# generic_micro_2.net
KiCad netlist of a schematic drawn in EAGLE
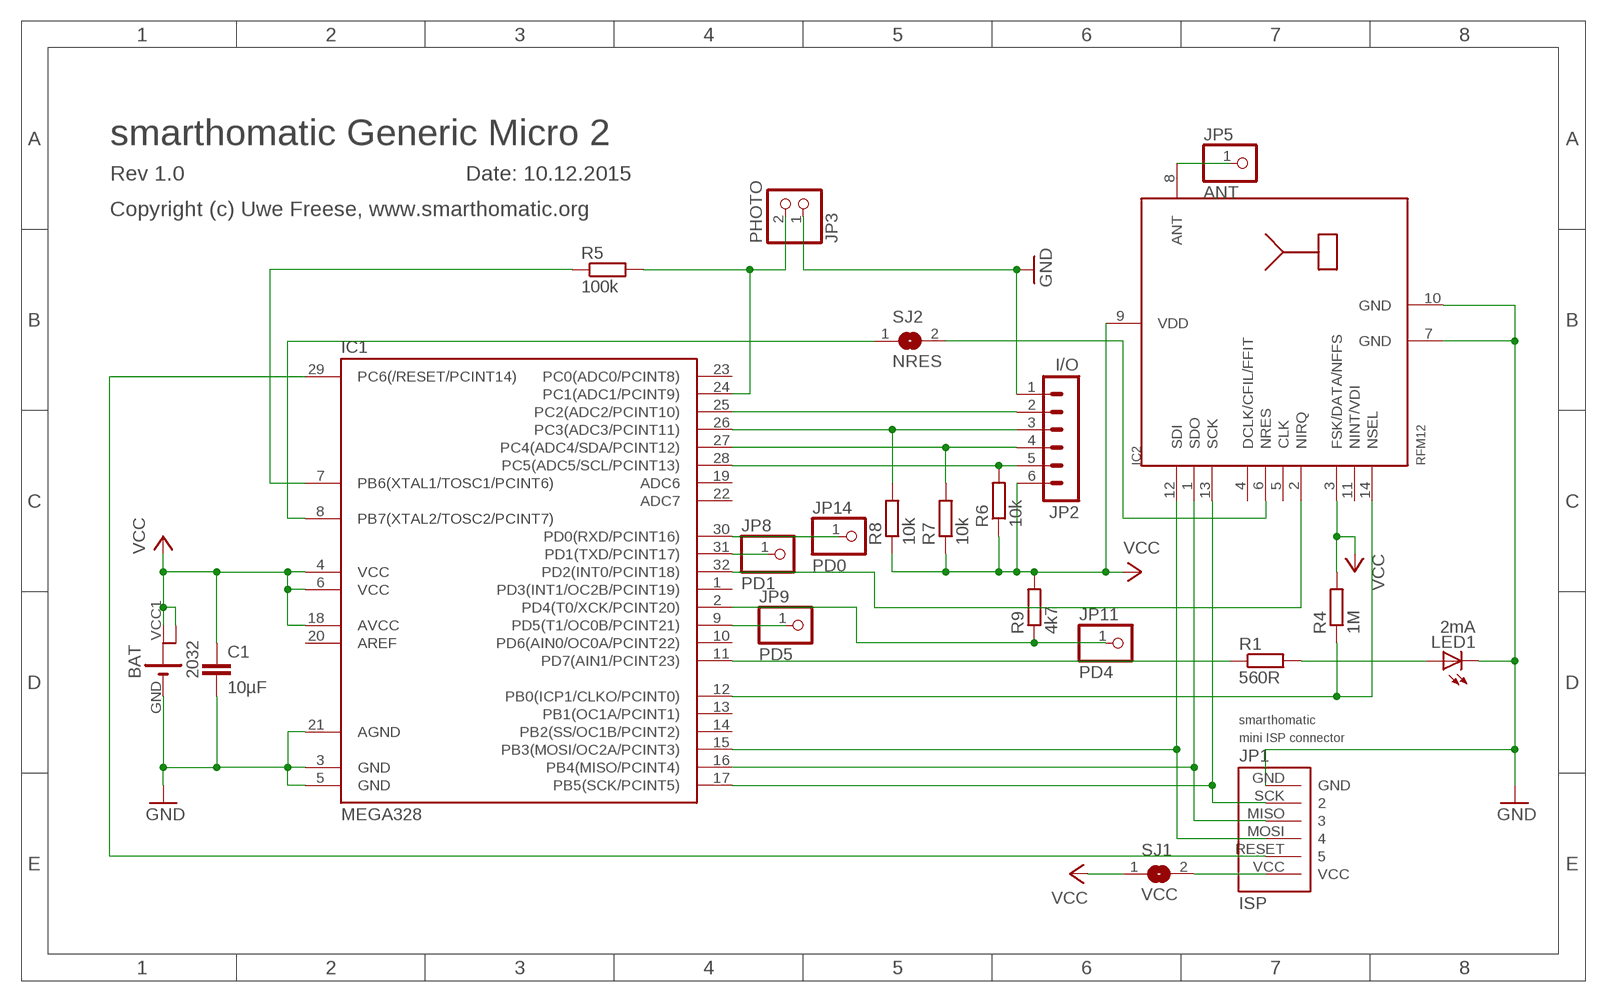
[diagram p0: schematic, sheet 1]

(export (version "E")
  (design (tool "Eeschema 10.0.6"))
  (components
    (comp (ref "BAT")
      (value "2032")
      (footprint "eagle-import:KZH20SMD")
      (libsource (lib "eagle-import") (part "2032"))
    )
    (comp (ref "C1")
      (value "10µF")
      (footprint "eagle-import:C0603")
      (libsource (lib "eagle-import") (part "C-EUC0603"))
    )
    (comp (ref "IC1")
      (value "MEGA328")
      (footprint "eagle-import:TQFP32-08")
      (libsource (lib "eagle-import") (part "MEGA48/88/168-AU"))
    )
    (comp (ref "IC2")
      (value "RFM12")
      (footprint "eagle-import:RFM")
      (libsource (lib "eagle-import") (part "RFM12"))
    )
    (comp (ref "JP1")
      (value "ISP")
      (footprint "eagle-import:PINHD_1X6_1.27")
      (libsource (lib "eagle-import") (part "SHC_MINI_ISPP"))
    )
    (comp (ref "JP2")
      (value "I/O")
      (footprint "eagle-import:MA06-1")
      (libsource (lib "eagle-import") (part "MA06-1"))
    )
    (comp (ref "JP3")
      (value "PHOTO")
      (footprint "eagle-import:1X02")
      (libsource (lib "eagle-import") (part "PINHD-1X2"))
    )
    (comp (ref "JP5")
      (value "ANT")
      (footprint "eagle-import:1X01")
      (libsource (lib "eagle-import") (part "PINHD-1X1"))
    )
    (comp (ref "JP8")
      (value "PD1")
      (footprint "eagle-import:1X01")
      (libsource (lib "eagle-import") (part "PINHD-1X1"))
    )
    (comp (ref "JP9")
      (value "PD5")
      (footprint "eagle-import:1X01")
      (libsource (lib "eagle-import") (part "PINHD-1X1"))
    )
    (comp (ref "JP11")
      (value "PD4")
      (footprint "eagle-import:1X01")
      (libsource (lib "eagle-import") (part "PINHD-1X1"))
    )
    (comp (ref "JP14")
      (value "PD0")
      (footprint "eagle-import:1X01")
      (libsource (lib "eagle-import") (part "PINHD-1X1"))
    )
    (comp (ref "LED1")
      (value "2mA")
      (footprint "eagle-import:LED3MM")
      (libsource (lib "eagle-import") (part "LED3MM"))
    )
    (comp (ref "R1")
      (value "560R")
      (footprint "eagle-import:R0603")
      (libsource (lib "eagle-import") (part "R-EU_R0603"))
    )
    (comp (ref "R4")
      (value "1M")
      (footprint "eagle-import:R0603")
      (libsource (lib "eagle-import") (part "R-EU_R0603"))
    )
    (comp (ref "R5")
      (value "100k")
      (footprint "eagle-import:R0603")
      (libsource (lib "eagle-import") (part "R-EU_R0603"))
    )
    (comp (ref "R6")
      (value "10k")
      (footprint "eagle-import:R0603")
      (libsource (lib "eagle-import") (part "R-EU_R0603"))
    )
    (comp (ref "R7")
      (value "10k")
      (footprint "eagle-import:R0603")
      (libsource (lib "eagle-import") (part "R-EU_R0603"))
    )
    (comp (ref "R8")
      (value "10k")
      (footprint "eagle-import:R0603")
      (libsource (lib "eagle-import") (part "R-EU_R0603"))
    )
    (comp (ref "R9")
      (value "4k7")
      (footprint "eagle-import:R0603")
      (libsource (lib "eagle-import") (part "R-EU_R0603"))
    )
    (comp (ref "SJ1")
      (value "VCC")
      (footprint "eagle-import:SJ")
      (libsource (lib "eagle-import") (part "SJ"))
    )
    (comp (ref "SJ2")
      (value "NRES")
      (footprint "eagle-import:SJ")
      (libsource (lib "eagle-import") (part "SJ"))
    )
  )
  (nets
    (net (code "1") (name "GND") (class "Default")
      (node (ref "BAT") (pin "GND") (pinfunction "GND_GND") (pintype "power_in"))
      (node (ref "C1") (pin "2") (pinfunction "2_2") (pintype "passive"))
      (node (ref "IC1") (pin "21") (pinfunction "AGND_21") (pintype "power_in"))
      (node (ref "IC1") (pin "3") (pinfunction "GND_3") (pintype "power_in"))
      (node (ref "IC1") (pin "5") (pinfunction "GND_5") (pintype "power_in"))
      (node (ref "IC2") (pin "10") (pinfunction "GND_10") (pintype "power_in"))
      (node (ref "IC2") (pin "7") (pinfunction "GND_7") (pintype "power_in"))
      (node (ref "JP1") (pin "GND") (pinfunction "GND_GND") (pintype "power_in"))
      (node (ref "JP2") (pin "1") (pinfunction "1_1") (pintype "passive"))
      (node (ref "JP3") (pin "1") (pinfunction "1_1") (pintype "passive"))
      (node (ref "LED1") (pin "K") (pinfunction "C_K") (pintype "passive"))
    )
    (net (code "2") (name "Net-(IC1-PB0(ICP1{slash}CLKO{slash}PCINT0))") (class "Default")
      (node (ref "IC1") (pin "12") (pinfunction "PB0(ICP1/CLKO/PCINT0)_12") (pintype "bidirectional"))
      (node (ref "IC2") (pin "14") (pinfunction "NSEL_14") (pintype "bidirectional"))
      (node (ref "R4") (pin "1") (pinfunction "1_1") (pintype "passive"))
    )
    (net (code "3") (name "Net-(IC1-PB3(MOSI{slash}OC2A{slash}PCINT3))") (class "Default")
      (node (ref "IC1") (pin "15") (pinfunction "PB3(MOSI/OC2A/PCINT3)_15") (pintype "bidirectional"))
      (node (ref "IC2") (pin "12") (pinfunction "SDI_12") (pintype "bidirectional"))
      (node (ref "JP1") (pin "MOSI") (pinfunction "4_MOSI") (pintype "output"))
    )
    (net (code "4") (name "Net-(IC1-PB4(MISO{slash}PCINT4))") (class "Default")
      (node (ref "IC1") (pin "16") (pinfunction "PB4(MISO/PCINT4)_16") (pintype "bidirectional"))
      (node (ref "IC2") (pin "1") (pinfunction "SDO_1") (pintype "bidirectional"))
      (node (ref "JP1") (pin "MISO") (pinfunction "3_MISO") (pintype "bidirectional"))
    )
    (net (code "5") (name "Net-(IC1-PB5(SCK{slash}PCINT5))") (class "Default")
      (node (ref "IC1") (pin "17") (pinfunction "PB5(SCK/PCINT5)_17") (pintype "bidirectional"))
      (node (ref "IC2") (pin "13") (pinfunction "SCK_13") (pintype "bidirectional"))
      (node (ref "JP1") (pin "SCK") (pinfunction "2_SCK") (pintype "output"))
    )
    (net (code "6") (name "Net-(IC1-PB6(XTAL1{slash}TOSC1{slash}PCINT6))") (class "Default")
      (node (ref "IC1") (pin "7") (pinfunction "PB6(XTAL1/TOSC1/PCINT6)_7") (pintype "bidirectional"))
      (node (ref "R5") (pin "1") (pinfunction "1_1") (pintype "passive"))
    )
    (net (code "7") (name "Net-(IC1-PB7(XTAL2{slash}TOSC2{slash}PCINT7))") (class "Default")
      (node (ref "IC1") (pin "8") (pinfunction "PB7(XTAL2/TOSC2/PCINT7)_8") (pintype "bidirectional"))
      (node (ref "SJ2") (pin "1") (pinfunction "1_1") (pintype "passive"))
    )
    (net (code "8") (name "Net-(IC1-PC1(ADC1{slash}PCINT9))") (class "Default")
      (node (ref "IC1") (pin "24") (pinfunction "PC1(ADC1/PCINT9)_24") (pintype "bidirectional"))
      (node (ref "JP3") (pin "2") (pinfunction "2_2") (pintype "passive"))
      (node (ref "R5") (pin "2") (pinfunction "2_2") (pintype "passive"))
    )
    (net (code "9") (name "Net-(IC1-PC2(ADC2{slash}PCINT10))") (class "Default")
      (node (ref "IC1") (pin "25") (pinfunction "PC2(ADC2/PCINT10)_25") (pintype "bidirectional"))
      (node (ref "JP2") (pin "2") (pinfunction "2_2") (pintype "passive"))
    )
    (net (code "10") (name "Net-(IC1-PC3(ADC3{slash}PCINT11))") (class "Default")
      (node (ref "IC1") (pin "26") (pinfunction "PC3(ADC3/PCINT11)_26") (pintype "bidirectional"))
      (node (ref "JP2") (pin "3") (pinfunction "3_3") (pintype "passive"))
      (node (ref "R8") (pin "2") (pinfunction "2_2") (pintype "passive"))
    )
    (net (code "11") (name "Net-(IC1-PC4(ADC4{slash}SDA{slash}PCINT12))") (class "Default")
      (node (ref "IC1") (pin "27") (pinfunction "PC4(ADC4/SDA/PCINT12)_27") (pintype "bidirectional"))
      (node (ref "JP2") (pin "4") (pinfunction "4_4") (pintype "passive"))
      (node (ref "R7") (pin "2") (pinfunction "2_2") (pintype "passive"))
    )
    (net (code "12") (name "Net-(IC1-PC5(ADC5{slash}SCL{slash}PCINT13))") (class "Default")
      (node (ref "IC1") (pin "28") (pinfunction "PC5(ADC5/SCL/PCINT13)_28") (pintype "bidirectional"))
      (node (ref "JP2") (pin "5") (pinfunction "5_5") (pintype "passive"))
      (node (ref "R6") (pin "2") (pinfunction "2_2") (pintype "passive"))
    )
    (net (code "13") (name "Net-(IC1-PC6({slash}RESET{slash}PCINT14))") (class "Default")
      (node (ref "IC1") (pin "29") (pinfunction "PC6(/RESET/PCINT14)_29") (pintype "bidirectional"))
      (node (ref "JP1") (pin "RESET") (pinfunction "5_RESET") (pintype "output"))
    )
    (net (code "14") (name "Net-(IC1-PD0(RXD{slash}PCINT16))") (class "Default")
      (node (ref "IC1") (pin "30") (pinfunction "PD0(RXD/PCINT16)_30") (pintype "bidirectional"))
      (node (ref "JP14") (pin "1") (pinfunction "1_1") (pintype "passive"))
    )
    (net (code "15") (name "Net-(IC1-PD1(TXD{slash}PCINT17))") (class "Default")
      (node (ref "IC1") (pin "31") (pinfunction "PD1(TXD/PCINT17)_31") (pintype "bidirectional"))
      (node (ref "JP8") (pin "1") (pinfunction "1_1") (pintype "passive"))
    )
    (net (code "16") (name "Net-(IC1-PD2(INT0{slash}PCINT18))") (class "Default")
      (node (ref "IC1") (pin "32") (pinfunction "PD2(INT0/PCINT18)_32") (pintype "bidirectional"))
      (node (ref "IC2") (pin "2") (pinfunction "NIRQ_2") (pintype "bidirectional"))
    )
    (net (code "17") (name "Net-(IC1-PD4(T0{slash}XCK{slash}PCINT20))") (class "Default")
      (node (ref "IC1") (pin "2") (pinfunction "PD4(T0/XCK/PCINT20)_2") (pintype "bidirectional"))
      (node (ref "JP11") (pin "1") (pinfunction "1_1") (pintype "passive"))
      (node (ref "R9") (pin "1") (pinfunction "1_1") (pintype "passive"))
    )
    (net (code "18") (name "Net-(IC1-PD5(T1{slash}OC0B{slash}PCINT21))") (class "Default")
      (node (ref "IC1") (pin "9") (pinfunction "PD5(T1/OC0B/PCINT21)_9") (pintype "bidirectional"))
      (node (ref "JP9") (pin "1") (pinfunction "1_1") (pintype "passive"))
    )
    (net (code "19") (name "Net-(IC1-PD7(AIN1{slash}PCINT23))") (class "Default")
      (node (ref "IC1") (pin "11") (pinfunction "PD7(AIN1/PCINT23)_11") (pintype "bidirectional"))
      (node (ref "R1") (pin "1") (pinfunction "1_1") (pintype "passive"))
    )
    (net (code "20") (name "Net-(IC2-ANT)") (class "Default")
      (node (ref "IC2") (pin "8") (pinfunction "ANT_8") (pintype "output"))
      (node (ref "JP5") (pin "1") (pinfunction "1_1") (pintype "passive"))
    )
    (net (code "21") (name "Net-(IC2-NRES)") (class "Default")
      (node (ref "IC2") (pin "6") (pinfunction "NRES_6") (pintype "bidirectional"))
      (node (ref "SJ2") (pin "2") (pinfunction "2_2") (pintype "passive"))
    )
    (net (code "22") (name "Net-(JP1-PadVCC)") (class "Default")
      (node (ref "JP1") (pin "VCC") (pinfunction "VCC_VCC") (pintype "power_in"))
      (node (ref "SJ1") (pin "2") (pinfunction "2_2") (pintype "passive"))
    )
    (net (code "23") (name "Net-(LED1-PadA)") (class "Default")
      (node (ref "LED1") (pin "A") (pinfunction "A_A") (pintype "passive"))
      (node (ref "R1") (pin "2") (pinfunction "2_2") (pintype "passive"))
    )
    (net (code "24") (name "VCC") (class "Default")
      (node (ref "BAT") (pin "VCC1") (pinfunction "VCC1_VCC1") (pintype "power_in"))
      (node (ref "BAT") (pin "VCC2") (pinfunction "VCC2_VCC2") (pintype "power_in"))
      (node (ref "C1") (pin "1") (pinfunction "1_1") (pintype "passive"))
      (node (ref "IC1") (pin "18") (pinfunction "AVCC_18") (pintype "passive"))
      (node (ref "IC1") (pin "4") (pinfunction "VCC_4") (pintype "power_in"))
      (node (ref "IC1") (pin "6") (pinfunction "VCC_6") (pintype "power_in"))
      (node (ref "IC2") (pin "3") (pinfunction "FSK/DATA/NFFS_3") (pintype "bidirectional"))
      (node (ref "IC2") (pin "9") (pinfunction "VDD_9") (pintype "power_in"))
      (node (ref "JP2") (pin "6") (pinfunction "6_6") (pintype "passive"))
      (node (ref "R4") (pin "2") (pinfunction "2_2") (pintype "passive"))
      (node (ref "R6") (pin "1") (pinfunction "1_1") (pintype "passive"))
      (node (ref "R7") (pin "1") (pinfunction "1_1") (pintype "passive"))
      (node (ref "R8") (pin "1") (pinfunction "1_1") (pintype "passive"))
      (node (ref "R9") (pin "2") (pinfunction "2_2") (pintype "passive"))
      (node (ref "SJ1") (pin "1") (pinfunction "1_1") (pintype "passive"))
    )
    (net (code "25") (name "unconnected-(IC1-ADC6-Pad19)") (class "Default")
      (node (ref "IC1") (pin "19") (pinfunction "ADC6_19") (pintype "passive"))
    )
    (net (code "26") (name "unconnected-(IC1-ADC7-Pad22)") (class "Default")
      (node (ref "IC1") (pin "22") (pinfunction "ADC7_22") (pintype "passive"))
    )
    (net (code "27") (name "unconnected-(IC1-AREF-Pad20)") (class "Default")
      (node (ref "IC1") (pin "20") (pinfunction "AREF_20") (pintype "passive"))
    )
    (net (code "28") (name "unconnected-(IC1-PB1(OC1A{slash}PCINT1)-Pad13)") (class "Default")
      (node (ref "IC1") (pin "13") (pinfunction "PB1(OC1A/PCINT1)_13") (pintype "bidirectional"))
    )
    (net (code "29") (name "unconnected-(IC1-PB2(SS{slash}OC1B{slash}PCINT2)-Pad14)") (class "Default")
      (node (ref "IC1") (pin "14") (pinfunction "PB2(SS/OC1B/PCINT2)_14") (pintype "bidirectional"))
    )
    (net (code "30") (name "unconnected-(IC1-PC0(ADC0{slash}PCINT8)-Pad23)") (class "Default")
      (node (ref "IC1") (pin "23") (pinfunction "PC0(ADC0/PCINT8)_23") (pintype "bidirectional"))
    )
    (net (code "31") (name "unconnected-(IC1-PD3(INT1{slash}OC2B{slash}PCINT19)-Pad1)") (class "Default")
      (node (ref "IC1") (pin "1") (pinfunction "PD3(INT1/OC2B/PCINT19)_1") (pintype "bidirectional"))
    )
    (net (code "32") (name "unconnected-(IC1-PD6(AIN0{slash}OC0A{slash}PCINT22)-Pad10)") (class "Default")
      (node (ref "IC1") (pin "10") (pinfunction "PD6(AIN0/OC0A/PCINT22)_10") (pintype "bidirectional"))
    )
    (net (code "33") (name "unconnected-(IC2-CLK-Pad5)") (class "Default")
      (node (ref "IC2") (pin "5") (pinfunction "CLK_5") (pintype "bidirectional"))
    )
    (net (code "34") (name "unconnected-(IC2-DCLK{slash}CFIL{slash}FFIT-Pad4)") (class "Default")
      (node (ref "IC2") (pin "4") (pinfunction "DCLK/CFIL/FFIT_4") (pintype "bidirectional"))
    )
    (net (code "35") (name "unconnected-(IC2-NINT{slash}VDI-Pad11)") (class "Default")
      (node (ref "IC2") (pin "11") (pinfunction "NINT/VDI_11") (pintype "bidirectional"))
    )
  )
)
